# StuderA80ReproExtend_V0_1.net
KiCad netlist of a schematic drawn in Altium Designer
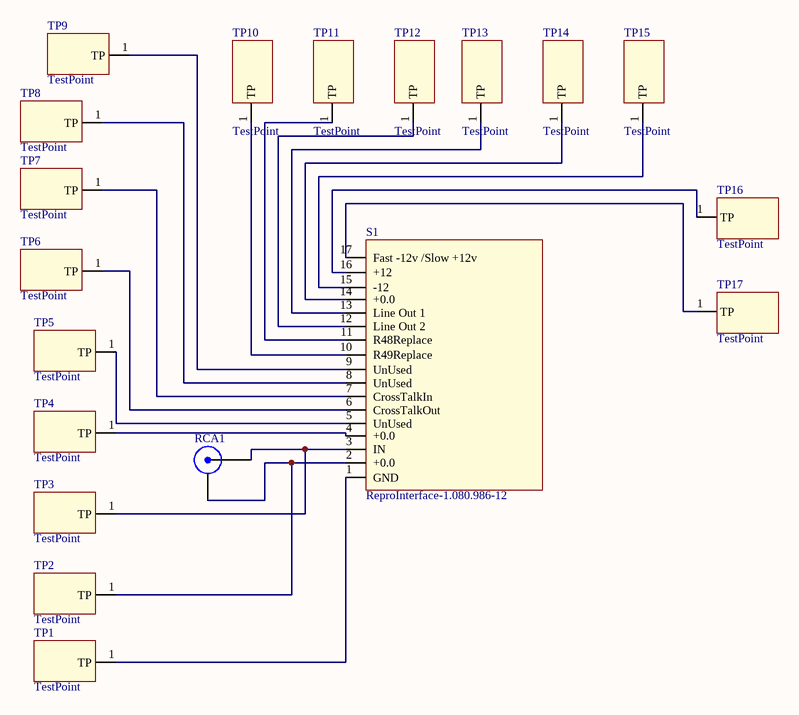
[diagram p0: StuderA80ReproExtend_V0.1.SchDoc]

(export (version "E")
  (design (tool "Eeschema 10.0.6"))
  (components
    (comp (ref "RCA1")
      (value "RCA")
      (footprint "RCA-RJ255")
      (description "RCA Connector")
      (fields (field (name "PUBLISHER") "Altium Limited"))
      (libsource (lib "Connectors") (part "RCA"))
    )
    (comp (ref "S1")
      (value "ReproInterface-1.080.986-12")
      (footprint "ReproInterface")
      (description "Studer A80 RC Reproduce Card 1.080.986-12 Interface")
      (libsource (lib "Studer") (part "ReproInterface-1.080.986-12"))
    )
    (comp (ref "TP1") (value "TestPoint") (footprint "TP-1.0mm") (libsource (lib "") (part "TestPoint_1")))
    (comp (ref "TP2") (value "TestPoint") (footprint "TP-1.0mm") (libsource (lib "") (part "TestPoint_1")))
    (comp (ref "TP3") (value "TestPoint") (footprint "TP-1.0mm") (libsource (lib "") (part "TestPoint_1")))
    (comp (ref "TP4") (value "TestPoint") (footprint "TP-1.0mm") (libsource (lib "") (part "TestPoint_1")))
    (comp (ref "TP5") (value "TestPoint") (footprint "TP-1.0mm") (libsource (lib "") (part "TestPoint_1")))
    (comp (ref "TP6") (value "TestPoint") (footprint "TP-1.0mm") (libsource (lib "") (part "TestPoint_1")))
    (comp (ref "TP7") (value "TestPoint") (footprint "TP-1.0mm") (libsource (lib "") (part "TestPoint_1")))
    (comp (ref "TP8") (value "TestPoint") (footprint "TP-1.0mm") (libsource (lib "") (part "TestPoint_1")))
    (comp (ref "TP9") (value "TestPoint") (footprint "TP-1.0mm") (libsource (lib "") (part "TestPoint_1")))
    (comp (ref "TP10")
      (value "TestPoint")
      (footprint "TP-1.0mm")
      (libsource (lib "Studer") (part "TestPoint"))
    )
    (comp (ref "TP11")
      (value "TestPoint")
      (footprint "TP-1.0mm")
      (libsource (lib "Studer") (part "TestPoint"))
    )
    (comp (ref "TP12")
      (value "TestPoint")
      (footprint "TP-1.0mm")
      (libsource (lib "Studer") (part "TestPoint"))
    )
    (comp (ref "TP13")
      (value "TestPoint")
      (footprint "TP-1.0mm")
      (libsource (lib "Studer") (part "TestPoint"))
    )
    (comp (ref "TP14")
      (value "TestPoint")
      (footprint "TP-1.0mm")
      (libsource (lib "Studer") (part "TestPoint"))
    )
    (comp (ref "TP15")
      (value "TestPoint")
      (footprint "TP-1.0mm")
      (libsource (lib "Studer") (part "TestPoint"))
    )
    (comp (ref "TP16") (value "TestPoint") (footprint "TP-1.0mm") (libsource (lib "") (part "TestPoint_2")))
    (comp (ref "TP17") (value "TestPoint") (footprint "TP-1.0mm") (libsource (lib "") (part "TestPoint_2")))
  )
  (nets
    (net (code "1") (name "Net-(RCA1-X)") (class "Default")
      (node (ref "RCA1") (pin "1") (pinfunction "X_1") (pintype "passive"))
      (node (ref "S1") (pin "3") (pinfunction "IN_3") (pintype "passive"))
      (node (ref "TP3") (pin "1") (pinfunction "TP_1") (pintype "passive"))
    )
    (net (code "2") (name "Net-(RCA1-Y)") (class "Default")
      (node (ref "RCA1") (pin "2") (pinfunction "Y_2") (pintype "passive"))
      (node (ref "S1") (pin "2") (pinfunction "+0.0_2") (pintype "passive"))
      (node (ref "TP2") (pin "1") (pinfunction "TP_1") (pintype "passive"))
    )
    (net (code "3") (name "Net-(S1-+12)") (class "Default")
      (node (ref "S1") (pin "16") (pinfunction "+12_16") (pintype "passive"))
      (node (ref "TP16") (pin "1") (pinfunction "TP_1") (pintype "passive"))
    )
    (net (code "4") (name "Net-(S1--12)") (class "Default")
      (node (ref "S1") (pin "15") (pinfunction "-12_15") (pintype "passive"))
      (node (ref "TP15") (pin "1") (pinfunction "TP_1") (pintype "passive"))
    )
    (net (code "5") (name "Net-(S1-CrossTalkIn)") (class "Default")
      (node (ref "S1") (pin "7") (pinfunction "CrossTalkIn_7") (pintype "passive"))
      (node (ref "TP7") (pin "1") (pinfunction "TP_1") (pintype "passive"))
    )
    (net (code "6") (name "Net-(S1-CrossTalkOut)") (class "Default")
      (node (ref "S1") (pin "6") (pinfunction "CrossTalkOut_6") (pintype "passive"))
      (node (ref "TP6") (pin "1") (pinfunction "TP_1") (pintype "passive"))
    )
    (net (code "7") (name "Net-(S1-Fast_-12v_{slash}Slow_+12v)") (class "Default")
      (node (ref "S1") (pin "17") (pinfunction "Fast_-12v_/Slow_+12v_17") (pintype "passive"))
      (node (ref "TP17") (pin "1") (pinfunction "TP_1") (pintype "passive"))
    )
    (net (code "8") (name "Net-(S1-GND)") (class "Default")
      (node (ref "S1") (pin "1") (pinfunction "GND_1") (pintype "passive"))
      (node (ref "TP1") (pin "1") (pinfunction "TP_1") (pintype "passive"))
    )
    (net (code "9") (name "Net-(S1-Line_Out_1)") (class "Default")
      (node (ref "S1") (pin "13") (pinfunction "Line_Out_1_13") (pintype "passive"))
      (node (ref "TP13") (pin "1") (pinfunction "TP_1") (pintype "passive"))
    )
    (net (code "10") (name "Net-(S1-Line_Out_2)") (class "Default")
      (node (ref "S1") (pin "12") (pinfunction "Line_Out_2_12") (pintype "passive"))
      (node (ref "TP12") (pin "1") (pinfunction "TP_1") (pintype "passive"))
    )
    (net (code "11") (name "Net-(S1-R48Replace)") (class "Default")
      (node (ref "S1") (pin "11") (pinfunction "R48Replace_11") (pintype "passive"))
      (node (ref "TP11") (pin "1") (pinfunction "TP_1") (pintype "passive"))
    )
    (net (code "12") (name "Net-(S1-R49Replace)") (class "Default")
      (node (ref "S1") (pin "10") (pinfunction "R49Replace_10") (pintype "passive"))
      (node (ref "TP10") (pin "1") (pinfunction "TP_1") (pintype "passive"))
    )
    (net (code "13") (name "Net-(TP4-TP)") (class "Default")
      (node (ref "S1") (pin "4") (pinfunction "+0.0_4") (pintype "passive"))
      (node (ref "TP4") (pin "1") (pinfunction "TP_1") (pintype "passive"))
    )
    (net (code "14") (name "Net-(TP5-TP)") (class "Default")
      (node (ref "S1") (pin "5") (pinfunction "UnUsed_5") (pintype "passive"))
      (node (ref "TP5") (pin "1") (pinfunction "TP_1") (pintype "passive"))
    )
    (net (code "15") (name "Net-(TP8-TP)") (class "Default")
      (node (ref "S1") (pin "8") (pinfunction "UnUsed_8") (pintype "passive"))
      (node (ref "TP8") (pin "1") (pinfunction "TP_1") (pintype "passive"))
    )
    (net (code "16") (name "Net-(TP9-TP)") (class "Default")
      (node (ref "S1") (pin "9") (pinfunction "UnUsed_9") (pintype "passive"))
      (node (ref "TP9") (pin "1") (pinfunction "TP_1") (pintype "passive"))
    )
    (net (code "17") (name "Net-(TP14-TP)") (class "Default")
      (node (ref "S1") (pin "14") (pinfunction "+0.0_14") (pintype "passive"))
      (node (ref "TP14") (pin "1") (pinfunction "TP_1") (pintype "passive"))
    )
  )
)
